# OptimuxPrimeSafe.net
KiCad netlist of a schematic drawn in EAGLE
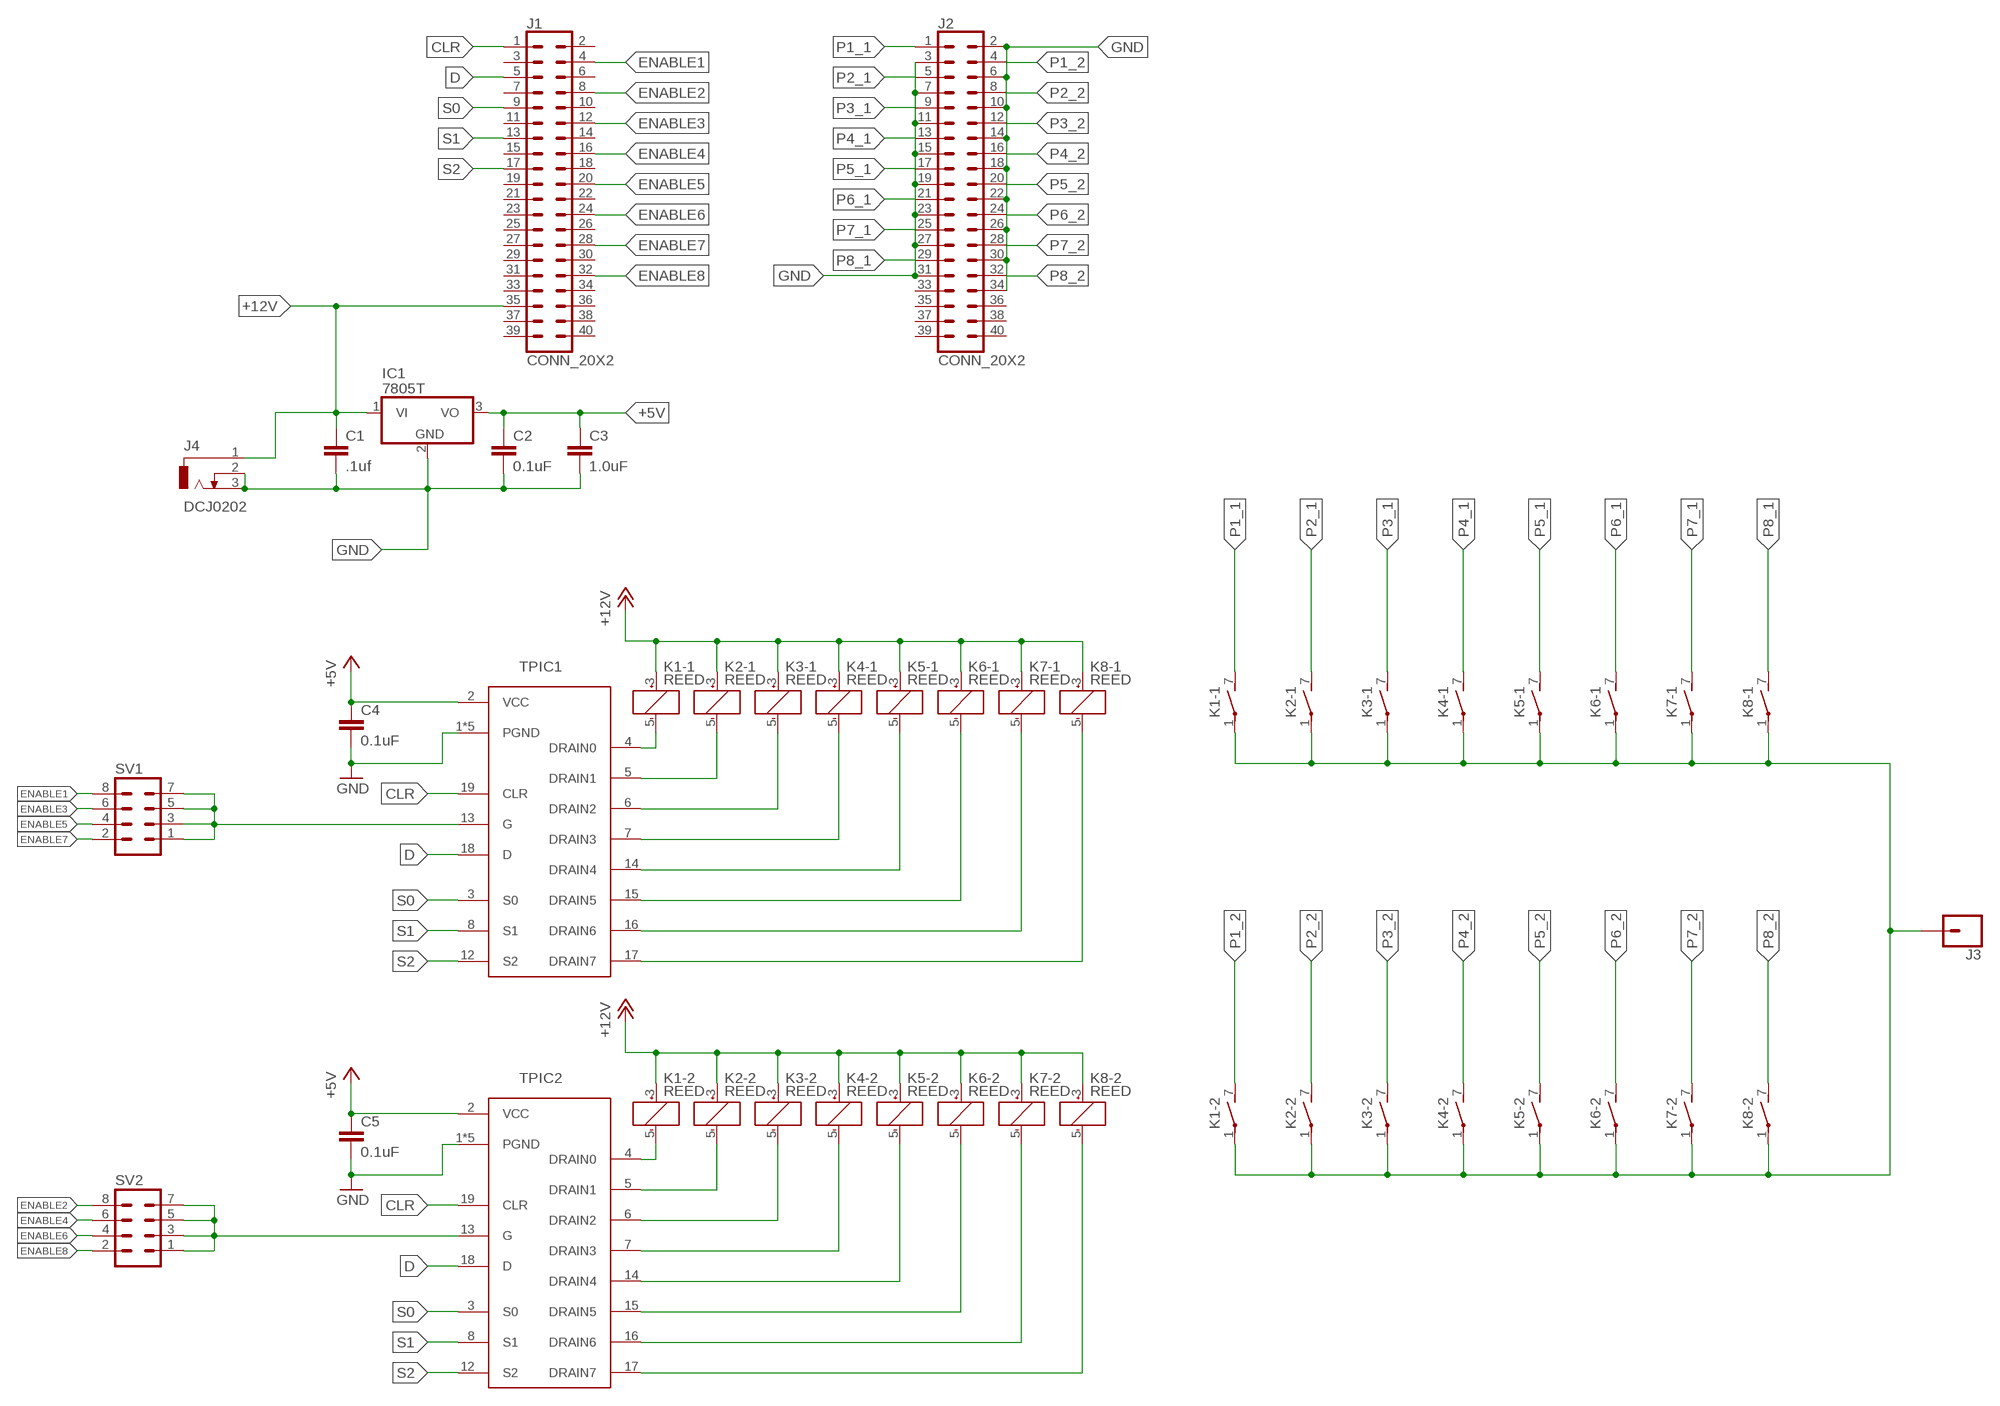
[diagram p0: schematic, sheet 1]

(export (version "E")
  (design (tool "Eeschema 10.0.6"))
  (components
    (comp (ref "C1")
      (value ".1uf")
      (footprint "eagle-import:0805")
      (libsource (lib "eagle-import") (part "1.0UF-0805-25V-(+80/-20%)"))
    )
    (comp (ref "C2")
      (value "0.1uF")
      (footprint "eagle-import:0805")
      (libsource (lib "eagle-import") (part "1.0UF-0805-25V-(+80/-20%)"))
    )
    (comp (ref "C3")
      (value "1.0uF")
      (footprint "eagle-import:0805")
      (libsource (lib "eagle-import") (part "1.0UF-0805-25V-(+80/-20%)"))
    )
    (comp (ref "C4")
      (value "0.1uF")
      (footprint "eagle-import:0805")
      (libsource (lib "eagle-import") (part "1.0UF-0805-25V-(+80/-20%)"))
    )
    (comp (ref "C5")
      (value "0.1uF")
      (footprint "eagle-import:0805")
      (libsource (lib "eagle-import") (part "1.0UF-0805-25V-(+80/-20%)"))
    )
    (comp (ref "IC1")
      (value "7805T")
      (footprint "eagle-import:TO220H")
      (libsource (lib "eagle-import") (part "78T05"))
    )
    (comp (ref "J1")
      (value "CONN_20X2")
      (footprint "eagle-import:2X20")
      (libsource (lib "eagle-import") (part "CONN_20X2"))
    )
    (comp (ref "J2")
      (value "CONN_20X2")
      (footprint "eagle-import:2X20")
      (libsource (lib "eagle-import") (part "CONN_20X2"))
    )
    (comp (ref "J3")
      (value "CONN_01")
      (footprint "eagle-import:1X01")
      (libsource (lib "eagle-import") (part "CONN_01"))
    )
    (comp (ref "J4")
      (value "DCJ0202")
      (footprint "eagle-import:DCJ0202")
      (libsource (lib "eagle-import") (part "DCJ0202"))
    )
    (comp (ref "K1-1")
      (value "REED")
      (footprint "eagle-import:REED")
      (libsource (lib "eagle-import") (part "REED"))
    )
    (comp (ref "K1-2")
      (value "REED")
      (footprint "eagle-import:REED")
      (libsource (lib "eagle-import") (part "REED"))
    )
    (comp (ref "K2-1")
      (value "REED")
      (footprint "eagle-import:REED")
      (libsource (lib "eagle-import") (part "REED"))
    )
    (comp (ref "K2-2")
      (value "REED")
      (footprint "eagle-import:REED")
      (libsource (lib "eagle-import") (part "REED"))
    )
    (comp (ref "K3-1")
      (value "REED")
      (footprint "eagle-import:REED")
      (libsource (lib "eagle-import") (part "REED"))
    )
    (comp (ref "K3-2")
      (value "REED")
      (footprint "eagle-import:REED")
      (libsource (lib "eagle-import") (part "REED"))
    )
    (comp (ref "K4-1")
      (value "REED")
      (footprint "eagle-import:REED")
      (libsource (lib "eagle-import") (part "REED"))
    )
    (comp (ref "K4-2")
      (value "REED")
      (footprint "eagle-import:REED")
      (libsource (lib "eagle-import") (part "REED"))
    )
    (comp (ref "K5-1")
      (value "REED")
      (footprint "eagle-import:REED")
      (libsource (lib "eagle-import") (part "REED"))
    )
    (comp (ref "K5-2")
      (value "REED")
      (footprint "eagle-import:REED")
      (libsource (lib "eagle-import") (part "REED"))
    )
    (comp (ref "K6-1")
      (value "REED")
      (footprint "eagle-import:REED")
      (libsource (lib "eagle-import") (part "REED"))
    )
    (comp (ref "K6-2")
      (value "REED")
      (footprint "eagle-import:REED")
      (libsource (lib "eagle-import") (part "REED"))
    )
    (comp (ref "K7-1")
      (value "REED")
      (footprint "eagle-import:REED")
      (libsource (lib "eagle-import") (part "REED"))
    )
    (comp (ref "K7-2")
      (value "REED")
      (footprint "eagle-import:REED")
      (libsource (lib "eagle-import") (part "REED"))
    )
    (comp (ref "K8-1")
      (value "REED")
      (footprint "eagle-import:REED")
      (libsource (lib "eagle-import") (part "REED"))
    )
    (comp (ref "K8-2")
      (value "REED")
      (footprint "eagle-import:REED")
      (libsource (lib "eagle-import") (part "REED"))
    )
    (comp (ref "SV1")
      (value "MA04-2")
      (footprint "eagle-import:MA04-2")
      (libsource (lib "eagle-import") (part "MA04-2"))
    )
    (comp (ref "SV2")
      (value "MA04-2")
      (footprint "eagle-import:MA04-2")
      (libsource (lib "eagle-import") (part "MA04-2"))
    )
    (comp (ref "TPIC1")
      (value "TPIC6259")
      (footprint "eagle-import:DIL20")
      (libsource (lib "eagle-import") (part "TPIC6259"))
    )
    (comp (ref "TPIC2")
      (value "TPIC6259")
      (footprint "eagle-import:DIL20")
      (libsource (lib "eagle-import") (part "TPIC6259"))
    )
  )
  (nets
    (net (code "1") (name "+5V") (class "Default")
      (node (ref "C2") (pin "1") (pinfunction "1_1") (pintype "passive"))
      (node (ref "C3") (pin "1") (pinfunction "1_1") (pintype "passive"))
      (node (ref "C4") (pin "1") (pinfunction "1_1") (pintype "passive"))
      (node (ref "C5") (pin "1") (pinfunction "1_1") (pintype "passive"))
      (node (ref "IC1") (pin "3") (pinfunction "VO_3") (pintype "passive"))
      (node (ref "TPIC1") (pin "2") (pinfunction "VCC_2") (pintype "bidirectional"))
      (node (ref "TPIC2") (pin "2") (pinfunction "VCC_2") (pintype "bidirectional"))
    )
    (net (code "2") (name "+12V") (class "Default")
      (node (ref "C1") (pin "1") (pinfunction "1_1") (pintype "passive"))
      (node (ref "IC1") (pin "1") (pinfunction "VI_1") (pintype "input"))
      (node (ref "J1") (pin "35") (pinfunction "35_35") (pintype "passive"))
      (node (ref "J4") (pin "1") (pinfunction "1_1") (pintype "passive"))
      (node (ref "K1-1") (pin "3") (pinfunction "+_3") (pintype "passive"))
      (node (ref "K1-2") (pin "3") (pinfunction "+_3") (pintype "passive"))
      (node (ref "K2-1") (pin "3") (pinfunction "+_3") (pintype "passive"))
      (node (ref "K2-2") (pin "3") (pinfunction "+_3") (pintype "passive"))
      (node (ref "K3-1") (pin "3") (pinfunction "+_3") (pintype "passive"))
      (node (ref "K3-2") (pin "3") (pinfunction "+_3") (pintype "passive"))
      (node (ref "K4-1") (pin "3") (pinfunction "+_3") (pintype "passive"))
      (node (ref "K4-2") (pin "3") (pinfunction "+_3") (pintype "passive"))
      (node (ref "K5-1") (pin "3") (pinfunction "+_3") (pintype "passive"))
      (node (ref "K5-2") (pin "3") (pinfunction "+_3") (pintype "passive"))
      (node (ref "K6-1") (pin "3") (pinfunction "+_3") (pintype "passive"))
      (node (ref "K6-2") (pin "3") (pinfunction "+_3") (pintype "passive"))
      (node (ref "K7-1") (pin "3") (pinfunction "+_3") (pintype "passive"))
      (node (ref "K7-2") (pin "3") (pinfunction "+_3") (pintype "passive"))
      (node (ref "K8-1") (pin "3") (pinfunction "+_3") (pintype "passive"))
      (node (ref "K8-2") (pin "3") (pinfunction "+_3") (pintype "passive"))
    )
    (net (code "3") (name "CLR") (class "Default")
      (node (ref "J1") (pin "1") (pinfunction "1_1") (pintype "passive"))
      (node (ref "TPIC1") (pin "19") (pinfunction "CLR_19") (pintype "bidirectional"))
      (node (ref "TPIC2") (pin "19") (pinfunction "CLR_19") (pintype "bidirectional"))
    )
    (net (code "4") (name "D") (class "Default")
      (node (ref "J1") (pin "5") (pinfunction "5_5") (pintype "passive"))
      (node (ref "TPIC1") (pin "18") (pinfunction "D_18") (pintype "bidirectional"))
      (node (ref "TPIC2") (pin "18") (pinfunction "D_18") (pintype "bidirectional"))
    )
    (net (code "5") (name "ENABLE1") (class "Default")
      (node (ref "J1") (pin "4") (pinfunction "4_4") (pintype "passive"))
      (node (ref "SV1") (pin "8") (pinfunction "8_8") (pintype "passive"))
    )
    (net (code "6") (name "ENABLE2") (class "Default")
      (node (ref "J1") (pin "8") (pinfunction "8_8") (pintype "passive"))
      (node (ref "SV2") (pin "8") (pinfunction "8_8") (pintype "passive"))
    )
    (net (code "7") (name "ENABLE3") (class "Default")
      (node (ref "J1") (pin "12") (pinfunction "12_12") (pintype "passive"))
      (node (ref "SV1") (pin "6") (pinfunction "6_6") (pintype "passive"))
    )
    (net (code "8") (name "ENABLE4") (class "Default")
      (node (ref "J1") (pin "16") (pinfunction "16_16") (pintype "passive"))
      (node (ref "SV2") (pin "6") (pinfunction "6_6") (pintype "passive"))
    )
    (net (code "9") (name "ENABLE5") (class "Default")
      (node (ref "J1") (pin "20") (pinfunction "20_20") (pintype "passive"))
      (node (ref "SV1") (pin "4") (pinfunction "4_4") (pintype "passive"))
    )
    (net (code "10") (name "ENABLE6") (class "Default")
      (node (ref "J1") (pin "24") (pinfunction "24_24") (pintype "passive"))
      (node (ref "SV2") (pin "4") (pinfunction "4_4") (pintype "passive"))
    )
    (net (code "11") (name "ENABLE7") (class "Default")
      (node (ref "J1") (pin "28") (pinfunction "28_28") (pintype "passive"))
      (node (ref "SV1") (pin "2") (pinfunction "2_2") (pintype "passive"))
    )
    (net (code "12") (name "ENABLE8") (class "Default")
      (node (ref "J1") (pin "32") (pinfunction "32_32") (pintype "passive"))
      (node (ref "SV2") (pin "2") (pinfunction "2_2") (pintype "passive"))
    )
    (net (code "13") (name "GND") (class "Default")
      (node (ref "C1") (pin "2") (pinfunction "2_2") (pintype "passive"))
      (node (ref "C2") (pin "2") (pinfunction "2_2") (pintype "passive"))
      (node (ref "C3") (pin "2") (pinfunction "2_2") (pintype "passive"))
      (node (ref "C4") (pin "2") (pinfunction "2_2") (pintype "passive"))
      (node (ref "C5") (pin "2") (pinfunction "2_2") (pintype "passive"))
      (node (ref "IC1") (pin "2") (pinfunction "GND_2") (pintype "passive"))
      (node (ref "J2") (pin "10") (pinfunction "10_10") (pintype "passive"))
      (node (ref "J2") (pin "11") (pinfunction "11_11") (pintype "passive"))
      (node (ref "J2") (pin "14") (pinfunction "14_14") (pintype "passive"))
      (node (ref "J2") (pin "15") (pinfunction "15_15") (pintype "passive"))
      (node (ref "J2") (pin "18") (pinfunction "18_18") (pintype "passive"))
      (node (ref "J2") (pin "19") (pinfunction "19_19") (pintype "passive"))
      (node (ref "J2") (pin "2") (pinfunction "2_2") (pintype "passive"))
      (node (ref "J2") (pin "22") (pinfunction "22_22") (pintype "passive"))
      (node (ref "J2") (pin "23") (pinfunction "23_23") (pintype "passive"))
      (node (ref "J2") (pin "26") (pinfunction "26_26") (pintype "passive"))
      (node (ref "J2") (pin "27") (pinfunction "27_27") (pintype "passive"))
      (node (ref "J2") (pin "3") (pinfunction "3_3") (pintype "passive"))
      (node (ref "J2") (pin "30") (pinfunction "30_30") (pintype "passive"))
      (node (ref "J2") (pin "31") (pinfunction "31_31") (pintype "passive"))
      (node (ref "J2") (pin "34") (pinfunction "34_34") (pintype "passive"))
      (node (ref "J2") (pin "6") (pinfunction "6_6") (pintype "passive"))
      (node (ref "J2") (pin "7") (pinfunction "7_7") (pintype "passive"))
      (node (ref "J4") (pin "2") (pinfunction "2_2") (pintype "passive"))
      (node (ref "J4") (pin "3") (pinfunction "3_3") (pintype "passive"))
      (node (ref "TPIC1") (pin "1") (pinfunction "PGND_1") (pintype "bidirectional"))
      (node (ref "TPIC1") (pin "10") (pinfunction "PGND_10") (pintype "bidirectional"))
      (node (ref "TPIC1") (pin "11") (pinfunction "PGND_11") (pintype "bidirectional"))
      (node (ref "TPIC1") (pin "20") (pinfunction "PGND_20") (pintype "bidirectional"))
      (node (ref "TPIC1") (pin "9") (pinfunction "PGND_9") (pintype "bidirectional"))
      (node (ref "TPIC2") (pin "1") (pinfunction "PGND_1") (pintype "bidirectional"))
      (node (ref "TPIC2") (pin "10") (pinfunction "PGND_10") (pintype "bidirectional"))
      (node (ref "TPIC2") (pin "11") (pinfunction "PGND_11") (pintype "bidirectional"))
      (node (ref "TPIC2") (pin "20") (pinfunction "PGND_20") (pintype "bidirectional"))
      (node (ref "TPIC2") (pin "9") (pinfunction "PGND_9") (pintype "bidirectional"))
    )
    (net (code "14") (name "Net-(K1-1A--)") (class "Default")
      (node (ref "K1-1") (pin "5") (pinfunction "-_5") (pintype "passive"))
      (node (ref "TPIC1") (pin "4") (pinfunction "DRAIN0_4") (pintype "bidirectional"))
    )
    (net (code "15") (name "Net-(K1-1B-P)") (class "Default")
      (node (ref "J3") (pin "1") (pinfunction "1_1") (pintype "passive"))
      (node (ref "K1-1") (pin "1") (pinfunction "P_1") (pintype "passive"))
      (node (ref "K1-2") (pin "1") (pinfunction "P_1") (pintype "passive"))
      (node (ref "K2-1") (pin "1") (pinfunction "P_1") (pintype "passive"))
      (node (ref "K2-2") (pin "1") (pinfunction "P_1") (pintype "passive"))
      (node (ref "K3-1") (pin "1") (pinfunction "P_1") (pintype "passive"))
      (node (ref "K3-2") (pin "1") (pinfunction "P_1") (pintype "passive"))
      (node (ref "K4-1") (pin "1") (pinfunction "P_1") (pintype "passive"))
      (node (ref "K4-2") (pin "1") (pinfunction "P_1") (pintype "passive"))
      (node (ref "K5-1") (pin "1") (pinfunction "P_1") (pintype "passive"))
      (node (ref "K5-2") (pin "1") (pinfunction "P_1") (pintype "passive"))
      (node (ref "K6-1") (pin "1") (pinfunction "P_1") (pintype "passive"))
      (node (ref "K6-2") (pin "1") (pinfunction "P_1") (pintype "passive"))
      (node (ref "K7-1") (pin "1") (pinfunction "P_1") (pintype "passive"))
      (node (ref "K7-2") (pin "1") (pinfunction "P_1") (pintype "passive"))
      (node (ref "K8-1") (pin "1") (pinfunction "P_1") (pintype "passive"))
      (node (ref "K8-2") (pin "1") (pinfunction "P_1") (pintype "passive"))
    )
    (net (code "16") (name "Net-(K1-2A--)") (class "Default")
      (node (ref "K1-2") (pin "5") (pinfunction "-_5") (pintype "passive"))
      (node (ref "TPIC2") (pin "4") (pinfunction "DRAIN0_4") (pintype "bidirectional"))
    )
    (net (code "17") (name "Net-(K2-1A--)") (class "Default")
      (node (ref "K2-1") (pin "5") (pinfunction "-_5") (pintype "passive"))
      (node (ref "TPIC1") (pin "5") (pinfunction "DRAIN1_5") (pintype "bidirectional"))
    )
    (net (code "18") (name "Net-(K2-2A--)") (class "Default")
      (node (ref "K2-2") (pin "5") (pinfunction "-_5") (pintype "passive"))
      (node (ref "TPIC2") (pin "5") (pinfunction "DRAIN1_5") (pintype "bidirectional"))
    )
    (net (code "19") (name "Net-(K3-1A--)") (class "Default")
      (node (ref "K3-1") (pin "5") (pinfunction "-_5") (pintype "passive"))
      (node (ref "TPIC1") (pin "6") (pinfunction "DRAIN2_6") (pintype "bidirectional"))
    )
    (net (code "20") (name "Net-(K3-2A--)") (class "Default")
      (node (ref "K3-2") (pin "5") (pinfunction "-_5") (pintype "passive"))
      (node (ref "TPIC2") (pin "6") (pinfunction "DRAIN2_6") (pintype "bidirectional"))
    )
    (net (code "21") (name "Net-(K4-1A--)") (class "Default")
      (node (ref "K4-1") (pin "5") (pinfunction "-_5") (pintype "passive"))
      (node (ref "TPIC1") (pin "7") (pinfunction "DRAIN3_7") (pintype "bidirectional"))
    )
    (net (code "22") (name "Net-(K4-2A--)") (class "Default")
      (node (ref "K4-2") (pin "5") (pinfunction "-_5") (pintype "passive"))
      (node (ref "TPIC2") (pin "7") (pinfunction "DRAIN3_7") (pintype "bidirectional"))
    )
    (net (code "23") (name "Net-(K5-1A--)") (class "Default")
      (node (ref "K5-1") (pin "5") (pinfunction "-_5") (pintype "passive"))
      (node (ref "TPIC1") (pin "14") (pinfunction "DRAIN4_14") (pintype "bidirectional"))
    )
    (net (code "24") (name "Net-(K5-2A--)") (class "Default")
      (node (ref "K5-2") (pin "5") (pinfunction "-_5") (pintype "passive"))
      (node (ref "TPIC2") (pin "14") (pinfunction "DRAIN4_14") (pintype "bidirectional"))
    )
    (net (code "25") (name "Net-(K6-1A--)") (class "Default")
      (node (ref "K6-1") (pin "5") (pinfunction "-_5") (pintype "passive"))
      (node (ref "TPIC1") (pin "15") (pinfunction "DRAIN5_15") (pintype "bidirectional"))
    )
    (net (code "26") (name "Net-(K6-2A--)") (class "Default")
      (node (ref "K6-2") (pin "5") (pinfunction "-_5") (pintype "passive"))
      (node (ref "TPIC2") (pin "15") (pinfunction "DRAIN5_15") (pintype "bidirectional"))
    )
    (net (code "27") (name "Net-(K7-1A--)") (class "Default")
      (node (ref "K7-1") (pin "5") (pinfunction "-_5") (pintype "passive"))
      (node (ref "TPIC1") (pin "16") (pinfunction "DRAIN6_16") (pintype "bidirectional"))
    )
    (net (code "28") (name "Net-(K7-2A--)") (class "Default")
      (node (ref "K7-2") (pin "5") (pinfunction "-_5") (pintype "passive"))
      (node (ref "TPIC2") (pin "16") (pinfunction "DRAIN6_16") (pintype "bidirectional"))
    )
    (net (code "29") (name "Net-(K8-1A--)") (class "Default")
      (node (ref "K8-1") (pin "5") (pinfunction "-_5") (pintype "passive"))
      (node (ref "TPIC1") (pin "17") (pinfunction "DRAIN7_17") (pintype "bidirectional"))
    )
    (net (code "30") (name "Net-(K8-2A--)") (class "Default")
      (node (ref "K8-2") (pin "5") (pinfunction "-_5") (pintype "passive"))
      (node (ref "TPIC2") (pin "17") (pinfunction "DRAIN7_17") (pintype "bidirectional"))
    )
    (net (code "31") (name "Net-(TPIC1-G)") (class "Default")
      (node (ref "SV1") (pin "1") (pinfunction "1_1") (pintype "passive"))
      (node (ref "SV1") (pin "3") (pinfunction "3_3") (pintype "passive"))
      (node (ref "SV1") (pin "5") (pinfunction "5_5") (pintype "passive"))
      (node (ref "SV1") (pin "7") (pinfunction "7_7") (pintype "passive"))
      (node (ref "TPIC1") (pin "13") (pinfunction "G_13") (pintype "bidirectional"))
    )
    (net (code "32") (name "Net-(TPIC2-G)") (class "Default")
      (node (ref "SV2") (pin "1") (pinfunction "1_1") (pintype "passive"))
      (node (ref "SV2") (pin "3") (pinfunction "3_3") (pintype "passive"))
      (node (ref "SV2") (pin "5") (pinfunction "5_5") (pintype "passive"))
      (node (ref "SV2") (pin "7") (pinfunction "7_7") (pintype "passive"))
      (node (ref "TPIC2") (pin "13") (pinfunction "G_13") (pintype "bidirectional"))
    )
    (net (code "33") (name "P1_1") (class "Default")
      (node (ref "J2") (pin "1") (pinfunction "1_1") (pintype "passive"))
      (node (ref "K1-1") (pin "7") (pinfunction "S_7") (pintype "passive"))
    )
    (net (code "34") (name "P1_2") (class "Default")
      (node (ref "J2") (pin "4") (pinfunction "4_4") (pintype "passive"))
      (node (ref "K1-2") (pin "7") (pinfunction "S_7") (pintype "passive"))
    )
    (net (code "35") (name "P2_1") (class "Default")
      (node (ref "J2") (pin "5") (pinfunction "5_5") (pintype "passive"))
      (node (ref "K2-1") (pin "7") (pinfunction "S_7") (pintype "passive"))
    )
    (net (code "36") (name "P2_2") (class "Default")
      (node (ref "J2") (pin "8") (pinfunction "8_8") (pintype "passive"))
      (node (ref "K2-2") (pin "7") (pinfunction "S_7") (pintype "passive"))
    )
    (net (code "37") (name "P3_1") (class "Default")
      (node (ref "J2") (pin "9") (pinfunction "9_9") (pintype "passive"))
      (node (ref "K3-1") (pin "7") (pinfunction "S_7") (pintype "passive"))
    )
    (net (code "38") (name "P3_2") (class "Default")
      (node (ref "J2") (pin "12") (pinfunction "12_12") (pintype "passive"))
      (node (ref "K3-2") (pin "7") (pinfunction "S_7") (pintype "passive"))
    )
    (net (code "39") (name "P4_1") (class "Default")
      (node (ref "J2") (pin "13") (pinfunction "13_13") (pintype "passive"))
      (node (ref "K4-1") (pin "7") (pinfunction "S_7") (pintype "passive"))
    )
    (net (code "40") (name "P4_2") (class "Default")
      (node (ref "J2") (pin "16") (pinfunction "16_16") (pintype "passive"))
      (node (ref "K4-2") (pin "7") (pinfunction "S_7") (pintype "passive"))
    )
    (net (code "41") (name "P5_1") (class "Default")
      (node (ref "J2") (pin "17") (pinfunction "17_17") (pintype "passive"))
      (node (ref "K5-1") (pin "7") (pinfunction "S_7") (pintype "passive"))
    )
    (net (code "42") (name "P5_2") (class "Default")
      (node (ref "J2") (pin "20") (pinfunction "20_20") (pintype "passive"))
      (node (ref "K5-2") (pin "7") (pinfunction "S_7") (pintype "passive"))
    )
    (net (code "43") (name "P6_1") (class "Default")
      (node (ref "J2") (pin "21") (pinfunction "21_21") (pintype "passive"))
      (node (ref "K6-1") (pin "7") (pinfunction "S_7") (pintype "passive"))
    )
    (net (code "44") (name "P6_2") (class "Default")
      (node (ref "J2") (pin "24") (pinfunction "24_24") (pintype "passive"))
      (node (ref "K6-2") (pin "7") (pinfunction "S_7") (pintype "passive"))
    )
    (net (code "45") (name "P7_1") (class "Default")
      (node (ref "J2") (pin "25") (pinfunction "25_25") (pintype "passive"))
      (node (ref "K7-1") (pin "7") (pinfunction "S_7") (pintype "passive"))
    )
    (net (code "46") (name "P7_2") (class "Default")
      (node (ref "J2") (pin "28") (pinfunction "28_28") (pintype "passive"))
      (node (ref "K7-2") (pin "7") (pinfunction "S_7") (pintype "passive"))
    )
    (net (code "47") (name "P8_1") (class "Default")
      (node (ref "J2") (pin "29") (pinfunction "29_29") (pintype "passive"))
      (node (ref "K8-1") (pin "7") (pinfunction "S_7") (pintype "passive"))
    )
    (net (code "48") (name "P8_2") (class "Default")
      (node (ref "J2") (pin "32") (pinfunction "32_32") (pintype "passive"))
      (node (ref "K8-2") (pin "7") (pinfunction "S_7") (pintype "passive"))
    )
    (net (code "49") (name "S0") (class "Default")
      (node (ref "J1") (pin "9") (pinfunction "9_9") (pintype "passive"))
      (node (ref "TPIC1") (pin "3") (pinfunction "S0_3") (pintype "bidirectional"))
      (node (ref "TPIC2") (pin "3") (pinfunction "S0_3") (pintype "bidirectional"))
    )
    (net (code "50") (name "S1") (class "Default")
      (node (ref "J1") (pin "13") (pinfunction "13_13") (pintype "passive"))
      (node (ref "TPIC1") (pin "8") (pinfunction "S1_8") (pintype "bidirectional"))
      (node (ref "TPIC2") (pin "8") (pinfunction "S1_8") (pintype "bidirectional"))
    )
    (net (code "51") (name "S2") (class "Default")
      (node (ref "J1") (pin "17") (pinfunction "17_17") (pintype "passive"))
      (node (ref "TPIC1") (pin "12") (pinfunction "S2_12") (pintype "bidirectional"))
      (node (ref "TPIC2") (pin "12") (pinfunction "S2_12") (pintype "bidirectional"))
    )
    (net (code "52") (name "unconnected-(J1-Pad2)") (class "Default")
      (node (ref "J1") (pin "2") (pinfunction "2_2") (pintype "passive"))
    )
    (net (code "53") (name "unconnected-(J1-Pad3)") (class "Default")
      (node (ref "J1") (pin "3") (pinfunction "3_3") (pintype "passive"))
    )
    (net (code "54") (name "unconnected-(J1-Pad6)") (class "Default")
      (node (ref "J1") (pin "6") (pinfunction "6_6") (pintype "passive"))
    )
    (net (code "55") (name "unconnected-(J1-Pad7)") (class "Default")
      (node (ref "J1") (pin "7") (pinfunction "7_7") (pintype "passive"))
    )
    (net (code "56") (name "unconnected-(J1-Pad10)") (class "Default")
      (node (ref "J1") (pin "10") (pinfunction "10_10") (pintype "passive"))
    )
    (net (code "57") (name "unconnected-(J1-Pad11)") (class "Default")
      (node (ref "J1") (pin "11") (pinfunction "11_11") (pintype "passive"))
    )
    (net (code "58") (name "unconnected-(J1-Pad14)") (class "Default")
      (node (ref "J1") (pin "14") (pinfunction "14_14") (pintype "passive"))
    )
    (net (code "59") (name "unconnected-(J1-Pad15)") (class "Default")
      (node (ref "J1") (pin "15") (pinfunction "15_15") (pintype "passive"))
    )
    (net (code "60") (name "unconnected-(J1-Pad18)") (class "Default")
      (node (ref "J1") (pin "18") (pinfunction "18_18") (pintype "passive"))
    )
    (net (code "61") (name "unconnected-(J1-Pad19)") (class "Default")
      (node (ref "J1") (pin "19") (pinfunction "19_19") (pintype "passive"))
    )
    (net (code "62") (name "unconnected-(J1-Pad21)") (class "Default")
      (node (ref "J1") (pin "21") (pinfunction "21_21") (pintype "passive"))
    )
    (net (code "63") (name "unconnected-(J1-Pad22)") (class "Default")
      (node (ref "J1") (pin "22") (pinfunction "22_22") (pintype "passive"))
    )
    (net (code "64") (name "unconnected-(J1-Pad23)") (class "Default")
      (node (ref "J1") (pin "23") (pinfunction "23_23") (pintype "passive"))
    )
    (net (code "65") (name "unconnected-(J1-Pad25)") (class "Default")
      (node (ref "J1") (pin "25") (pinfunction "25_25") (pintype "passive"))
    )
    (net (code "66") (name "unconnected-(J1-Pad26)") (class "Default")
      (node (ref "J1") (pin "26") (pinfunction "26_26") (pintype "passive"))
    )
    (net (code "67") (name "unconnected-(J1-Pad27)") (class "Default")
      (node (ref "J1") (pin "27") (pinfunction "27_27") (pintype "passive"))
    )
    (net (code "68") (name "unconnected-(J1-Pad29)") (class "Default")
      (node (ref "J1") (pin "29") (pinfunction "29_29") (pintype "passive"))
    )
    (net (code "69") (name "unconnected-(J1-Pad30)") (class "Default")
      (node (ref "J1") (pin "30") (pinfunction "30_30") (pintype "passive"))
    )
    (net (code "70") (name "unconnected-(J1-Pad31)") (class "Default")
      (node (ref "J1") (pin "31") (pinfunction "31_31") (pintype "passive"))
    )
    (net (code "71") (name "unconnected-(J1-Pad33)") (class "Default")
      (node (ref "J1") (pin "33") (pinfunction "33_33") (pintype "passive"))
    )
    (net (code "72") (name "unconnected-(J1-Pad34)") (class "Default")
      (node (ref "J1") (pin "34") (pinfunction "34_34") (pintype "passive"))
    )
    (net (code "73") (name "unconnected-(J1-Pad36)") (class "Default")
      (node (ref "J1") (pin "36") (pinfunction "36_36") (pintype "passive"))
    )
    (net (code "74") (name "unconnected-(J1-Pad37)") (class "Default")
      (node (ref "J1") (pin "37") (pinfunction "37_37") (pintype "passive"))
    )
    (net (code "75") (name "unconnected-(J1-Pad38)") (class "Default")
      (node (ref "J1") (pin "38") (pinfunction "38_38") (pintype "passive"))
    )
    (net (code "76") (name "unconnected-(J1-Pad39)") (class "Default")
      (node (ref "J1") (pin "39") (pinfunction "39_39") (pintype "passive"))
    )
    (net (code "77") (name "unconnected-(J1-Pad40)") (class "Default")
      (node (ref "J1") (pin "40") (pinfunction "40_40") (pintype "passive"))
    )
    (net (code "78") (name "unconnected-(J2-Pad33)") (class "Default")
      (node (ref "J2") (pin "33") (pinfunction "33_33") (pintype "passive"))
    )
    (net (code "79") (name "unconnected-(J2-Pad35)") (class "Default")
      (node (ref "J2") (pin "35") (pinfunction "35_35") (pintype "passive"))
    )
    (net (code "80") (name "unconnected-(J2-Pad36)") (class "Default")
      (node (ref "J2") (pin "36") (pinfunction "36_36") (pintype "passive"))
    )
    (net (code "81") (name "unconnected-(J2-Pad37)") (class "Default")
      (node (ref "J2") (pin "37") (pinfunction "37_37") (pintype "passive"))
    )
    (net (code "82") (name "unconnected-(J2-Pad38)") (class "Default")
      (node (ref "J2") (pin "38") (pinfunction "38_38") (pintype "passive"))
    )
    (net (code "83") (name "unconnected-(J2-Pad39)") (class "Default")
      (node (ref "J2") (pin "39") (pinfunction "39_39") (pintype "passive"))
    )
    (net (code "84") (name "unconnected-(J2-Pad40)") (class "Default")
      (node (ref "J2") (pin "40") (pinfunction "40_40") (pintype "passive"))
    )
  )
)
